# 5v_Regulator.net
KiCad netlist of a schematic drawn in Altium Designer
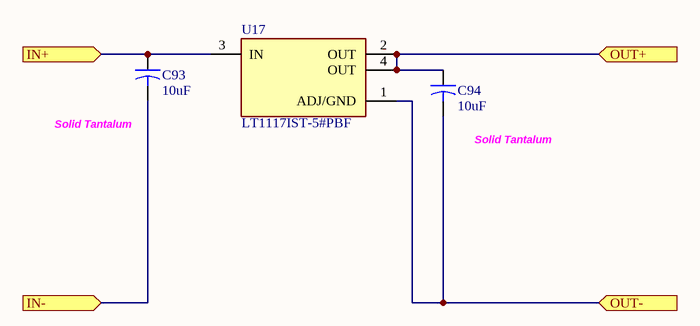
[diagram p0: 5v_Regulator.SchDoc]

(export (version "E")
  (design (tool "Eeschema 10.0.6"))
  (components
    (comp (ref "C93")
      (value "10uF")
      (footprint "Tantalum_2917")
      (description "Capacitor, 100uF NICHICON")
      (libsource (lib "Arturo_Approved") (part "UVR1V102MHD1TO"))
    )
    (comp (ref "C94")
      (value "10uF")
      (footprint "Tantalum_2917")
      (description "Capacitor, 100uF NICHICON")
      (libsource (lib "Arturo_Approved") (part "UVR1V102MHD1TO"))
    )
    (comp (ref "U17")
      (value "LT1117IST-5#PBF")
      (footprint "Arturo_Approved:REG_LT1117IST-5#PBF")
      (description "LDO Regulator Pos 5V 0.8A Automotive 4-Pin_3+Tab_ SOT-223 Tube")
      (fields (field (name "MF") "Analog Devices"))
      (libsource (lib "Arturo_Approved") (part "LT1117IST-5#PBF"))
    )
  )
  (nets
    (net (code "1") (name "/IN+") (class "Default")
      (node (ref "C93") (pin "1") (pinfunction "1_1") (pintype "passive"))
      (node (ref "U17") (pin "3") (pinfunction "IN_3") (pintype "passive"))
    )
    (net (code "2") (name "/IN-") (class "Default")
      (node (ref "C93") (pin "2") (pinfunction "2_2") (pintype "passive"))
    )
    (net (code "3") (name "/OUT+") (class "Default")
      (node (ref "C94") (pin "1") (pinfunction "1_1") (pintype "passive"))
      (node (ref "U17") (pin "2") (pinfunction "OUT_2") (pintype "passive"))
      (node (ref "U17") (pin "4") (pinfunction "OUT_4") (pintype "passive"))
    )
    (net (code "4") (name "/OUT-") (class "Default")
      (node (ref "C94") (pin "2") (pinfunction "2_2") (pintype "passive"))
      (node (ref "U17") (pin "1") (pinfunction "ADJ/GND_1") (pintype "power_in"))
    )
  )
)
